# closed-loop-control-v2.net
KiCad netlist of a schematic drawn in EAGLE
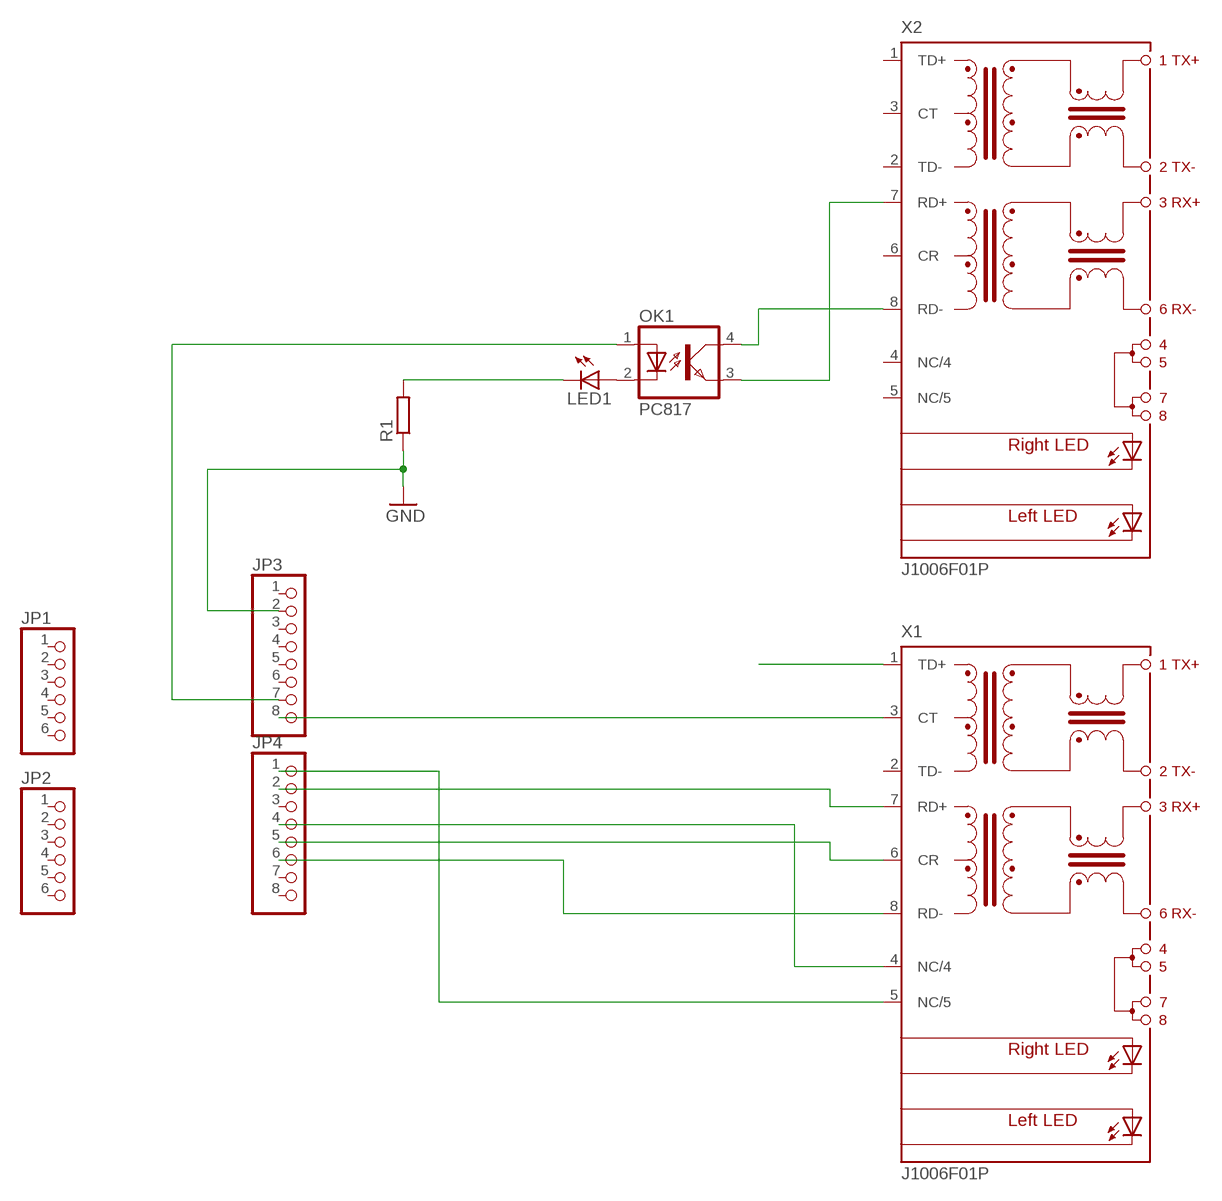
[diagram p0: schematic, sheet 1]

(export (version "E")
  (design (tool "Eeschema 10.0.6"))
  (components
    (comp (ref "JP1")
      (value "PINHD-1X6")
      (footprint "eagle-import:1X06")
      (libsource (lib "eagle-import") (part "PINHD-1X6"))
    )
    (comp (ref "JP2")
      (value "PINHD-1X6")
      (footprint "eagle-import:1X06")
      (libsource (lib "eagle-import") (part "PINHD-1X6"))
    )
    (comp (ref "JP3")
      (value "PINHD-1X8")
      (footprint "eagle-import:1X08")
      (libsource (lib "eagle-import") (part "PINHD-1X8"))
    )
    (comp (ref "JP4")
      (value "PINHD-1X8")
      (footprint "eagle-import:1X08")
      (libsource (lib "eagle-import") (part "PINHD-1X8"))
    )
    (comp (ref "LED1")
      (value "LED3MM")
      (footprint "eagle-import:LED3MM")
      (libsource (lib "eagle-import") (part "LED3MM"))
    )
    (comp (ref "OK1")
      (value "PC817")
      (footprint "eagle-import:DIL04")
      (fields (field (name "MPN") "PC817X4J000F"))
      (libsource (lib "eagle-import") (part "PC817"))
    )
    (comp (ref "R1")
      (value "R-EU_0207/10")
      (footprint "eagle-import:0207_10")
      (libsource (lib "eagle-import") (part "R-EU_0207/10"))
    )
    (comp (ref "X1")
      (value "J1006F01P")
      (footprint "eagle-import:J1")
      (libsource (lib "eagle-import") (part "J1006F01P"))
    )
    (comp (ref "X2")
      (value "J1006F01P")
      (footprint "eagle-import:J1")
      (libsource (lib "eagle-import") (part "J1006F01P"))
    )
  )
  (nets
    (net (code "1") (name "GND") (class "Default")
      (node (ref "JP3") (pin "2") (pinfunction "2_2") (pintype "passive"))
      (node (ref "R1") (pin "1") (pinfunction "1_1") (pintype "passive"))
      (node (ref "X1") (pin "1") (pinfunction "TD+_1") (pintype "input"))
    )
    (net (code "2") (name "Net-(LED1-C)") (class "Default")
      (node (ref "LED1") (pin "K") (pinfunction "C_K") (pintype "passive"))
      (node (ref "R1") (pin "2") (pinfunction "2_2") (pintype "passive"))
    )
    (net (code "3") (name "Net-(OK1-A)") (class "Default")
      (node (ref "JP3") (pin "7") (pinfunction "7_7") (pintype "passive"))
      (node (ref "OK1") (pin "1") (pinfunction "A_1") (pintype "passive"))
    )
    (net (code "4") (name "Net-(OK1-C)") (class "Default")
      (node (ref "LED1") (pin "A") (pinfunction "A_A") (pintype "passive"))
      (node (ref "OK1") (pin "2") (pinfunction "C_2") (pintype "passive"))
    )
    (net (code "5") (name "Net-(OK1-COL)") (class "Default")
      (node (ref "OK1") (pin "4") (pinfunction "COL_4") (pintype "passive"))
      (node (ref "X2") (pin "8") (pinfunction "RD-_8") (pintype "input"))
    )
    (net (code "6") (name "Net-(OK1-EMIT)") (class "Default")
      (node (ref "OK1") (pin "3") (pinfunction "EMIT_3") (pintype "passive"))
      (node (ref "X2") (pin "7") (pinfunction "RD+_7") (pintype "input"))
    )
    (net (code "7") (name "Net-(X1-CR)") (class "Default")
      (node (ref "JP4") (pin "5") (pinfunction "5_5") (pintype "passive"))
      (node (ref "X1") (pin "6") (pinfunction "CR_6") (pintype "input"))
    )
    (net (code "8") (name "Net-(X1-CT)") (class "Default")
      (node (ref "JP3") (pin "8") (pinfunction "8_8") (pintype "passive"))
      (node (ref "X1") (pin "3") (pinfunction "CT_3") (pintype "input"))
    )
    (net (code "9") (name "Net-(X1-NC{slash}4)") (class "Default")
      (node (ref "JP4") (pin "4") (pinfunction "4_4") (pintype "passive"))
      (node (ref "X1") (pin "4") (pinfunction "NC/4_4") (pintype "input"))
    )
    (net (code "10") (name "Net-(X1-NC{slash}5)") (class "Default")
      (node (ref "JP4") (pin "1") (pinfunction "1_1") (pintype "passive"))
      (node (ref "X1") (pin "5") (pinfunction "NC/5_5") (pintype "input"))
    )
    (net (code "11") (name "Net-(X1-RD+)") (class "Default")
      (node (ref "JP4") (pin "2") (pinfunction "2_2") (pintype "passive"))
      (node (ref "X1") (pin "7") (pinfunction "RD+_7") (pintype "input"))
    )
    (net (code "12") (name "Net-(X1-RD-)") (class "Default")
      (node (ref "JP4") (pin "6") (pinfunction "6_6") (pintype "passive"))
      (node (ref "X1") (pin "8") (pinfunction "RD-_8") (pintype "input"))
    )
    (net (code "13") (name "unconnected-(JP1-Pad1)") (class "Default")
      (node (ref "JP1") (pin "1") (pinfunction "1_1") (pintype "passive"))
    )
    (net (code "14") (name "unconnected-(JP1-Pad2)") (class "Default")
      (node (ref "JP1") (pin "2") (pinfunction "2_2") (pintype "passive"))
    )
    (net (code "15") (name "unconnected-(JP1-Pad3)") (class "Default")
      (node (ref "JP1") (pin "3") (pinfunction "3_3") (pintype "passive"))
    )
    (net (code "16") (name "unconnected-(JP1-Pad4)") (class "Default")
      (node (ref "JP1") (pin "4") (pinfunction "4_4") (pintype "passive"))
    )
    (net (code "17") (name "unconnected-(JP1-Pad5)") (class "Default")
      (node (ref "JP1") (pin "5") (pinfunction "5_5") (pintype "passive"))
    )
    (net (code "18") (name "unconnected-(JP1-Pad6)") (class "Default")
      (node (ref "JP1") (pin "6") (pinfunction "6_6") (pintype "passive"))
    )
    (net (code "19") (name "unconnected-(JP2-Pad1)") (class "Default")
      (node (ref "JP2") (pin "1") (pinfunction "1_1") (pintype "passive"))
    )
    (net (code "20") (name "unconnected-(JP2-Pad2)") (class "Default")
      (node (ref "JP2") (pin "2") (pinfunction "2_2") (pintype "passive"))
    )
    (net (code "21") (name "unconnected-(JP2-Pad3)") (class "Default")
      (node (ref "JP2") (pin "3") (pinfunction "3_3") (pintype "passive"))
    )
    (net (code "22") (name "unconnected-(JP2-Pad4)") (class "Default")
      (node (ref "JP2") (pin "4") (pinfunction "4_4") (pintype "passive"))
    )
    (net (code "23") (name "unconnected-(JP2-Pad5)") (class "Default")
      (node (ref "JP2") (pin "5") (pinfunction "5_5") (pintype "passive"))
    )
    (net (code "24") (name "unconnected-(JP2-Pad6)") (class "Default")
      (node (ref "JP2") (pin "6") (pinfunction "6_6") (pintype "passive"))
    )
    (net (code "25") (name "unconnected-(JP3-Pad1)") (class "Default")
      (node (ref "JP3") (pin "1") (pinfunction "1_1") (pintype "passive"))
    )
    (net (code "26") (name "unconnected-(JP3-Pad3)") (class "Default")
      (node (ref "JP3") (pin "3") (pinfunction "3_3") (pintype "passive"))
    )
    (net (code "27") (name "unconnected-(JP3-Pad4)") (class "Default")
      (node (ref "JP3") (pin "4") (pinfunction "4_4") (pintype "passive"))
    )
    (net (code "28") (name "unconnected-(JP3-Pad5)") (class "Default")
      (node (ref "JP3") (pin "5") (pinfunction "5_5") (pintype "passive"))
    )
    (net (code "29") (name "unconnected-(JP3-Pad6)") (class "Default")
      (node (ref "JP3") (pin "6") (pinfunction "6_6") (pintype "passive"))
    )
    (net (code "30") (name "unconnected-(JP4-Pad3)") (class "Default")
      (node (ref "JP4") (pin "3") (pinfunction "3_3") (pintype "passive"))
    )
    (net (code "31") (name "unconnected-(JP4-Pad7)") (class "Default")
      (node (ref "JP4") (pin "7") (pinfunction "7_7") (pintype "passive"))
    )
    (net (code "32") (name "unconnected-(JP4-Pad8)") (class "Default")
      (node (ref "JP4") (pin "8") (pinfunction "8_8") (pintype "passive"))
    )
    (net (code "33") (name "unconnected-(X1-TD--Pad2)") (class "Default")
      (node (ref "X1") (pin "2") (pinfunction "TD-_2") (pintype "input"))
    )
    (net (code "34") (name "unconnected-(X2-CR-Pad6)") (class "Default")
      (node (ref "X2") (pin "6") (pinfunction "CR_6") (pintype "input"))
    )
    (net (code "35") (name "unconnected-(X2-CT-Pad3)") (class "Default")
      (node (ref "X2") (pin "3") (pinfunction "CT_3") (pintype "input"))
    )
    (net (code "36") (name "unconnected-(X2-NC{slash}4-Pad4)") (class "Default")
      (node (ref "X2") (pin "4") (pinfunction "NC/4_4") (pintype "input"))
    )
    (net (code "37") (name "unconnected-(X2-NC{slash}5-Pad5)") (class "Default")
      (node (ref "X2") (pin "5") (pinfunction "NC/5_5") (pintype "input"))
    )
    (net (code "38") (name "unconnected-(X2-TD+-Pad1)") (class "Default")
      (node (ref "X2") (pin "1") (pinfunction "TD+_1") (pintype "input"))
    )
    (net (code "39") (name "unconnected-(X2-TD--Pad2)") (class "Default")
      (node (ref "X2") (pin "2") (pinfunction "TD-_2") (pintype "input"))
    )
  )
)
